# P9-Calculadora.net
KiCad netlist of a schematic drawn in EAGLE
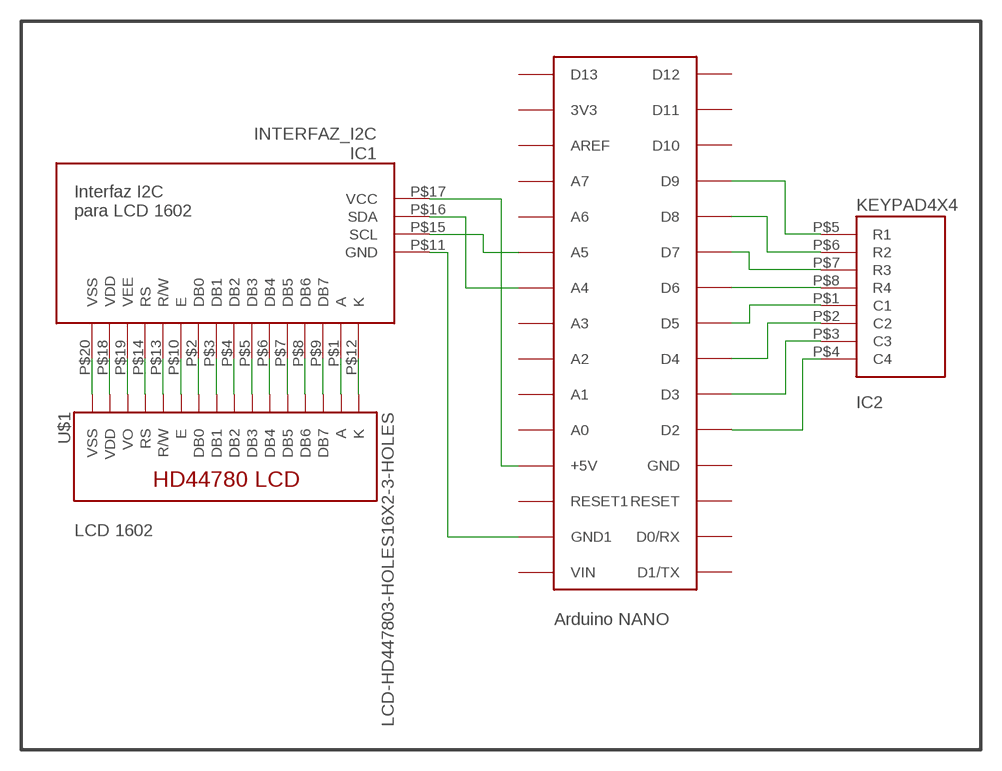
[diagram p0: schematic, sheet 1]

(export (version "E")
  (design (tool "Eeschema 10.0.6"))
  (components
    (comp (ref "IC1")
      (value "INTERFAZ_I2C")
      (footprint "eagle-import:NO_FOOTPRINT")
      (libsource (lib "eagle-import") (part "INTERFAZ_I2C"))
    )
    (comp (ref "IC2")
      (value "KEYPAD4X4")
      (footprint "eagle-import:NO_FOOTPRINT")
      (libsource (lib "eagle-import") (part "KEYPAD4X4"))
    )
    (comp (ref "U$1")
      (value "LCD-HD447803-HOLES16X2-3-HOLES")
      (footprint "eagle-import:LCD-16X2-3HOLES")
      (libsource (lib "eagle-import") (part "LCD-HD4478016X2-3-HOLES3-HOLES"))
    )
    (comp (ref "U$2")
      (value "ARDUINONANO")
      (footprint "eagle-import:PDIP-32")
      (libsource (lib "eagle-import") (part "ARDUINONANO"))
    )
  )
  (nets
    (net (code "1") (name "Net-(IC1-A)") (class "Default")
      (node (ref "IC1") (pin "P$1") (pinfunction "A_P$1") (pintype "bidirectional"))
      (node (ref "U$1") (pin "15") (pinfunction "A_15") (pintype "power_in"))
    )
    (net (code "2") (name "Net-(IC1-DB0)") (class "Default")
      (node (ref "IC1") (pin "P$2") (pinfunction "DB0_P$2") (pintype "bidirectional"))
      (node (ref "U$1") (pin "7") (pinfunction "DB0_7") (pintype "bidirectional"))
    )
    (net (code "3") (name "Net-(IC1-DB1)") (class "Default")
      (node (ref "IC1") (pin "P$3") (pinfunction "DB1_P$3") (pintype "bidirectional"))
      (node (ref "U$1") (pin "8") (pinfunction "DB1_8") (pintype "bidirectional"))
    )
    (net (code "4") (name "Net-(IC1-DB2)") (class "Default")
      (node (ref "IC1") (pin "P$4") (pinfunction "DB2_P$4") (pintype "bidirectional"))
      (node (ref "U$1") (pin "9") (pinfunction "DB2_9") (pintype "bidirectional"))
    )
    (net (code "5") (name "Net-(IC1-DB3)") (class "Default")
      (node (ref "IC1") (pin "P$5") (pinfunction "DB3_P$5") (pintype "bidirectional"))
      (node (ref "U$1") (pin "10") (pinfunction "DB3_10") (pintype "bidirectional"))
    )
    (net (code "6") (name "Net-(IC1-DB4)") (class "Default")
      (node (ref "IC1") (pin "P$6") (pinfunction "DB4_P$6") (pintype "bidirectional"))
      (node (ref "U$1") (pin "11") (pinfunction "DB4_11") (pintype "bidirectional"))
    )
    (net (code "7") (name "Net-(IC1-DB5)") (class "Default")
      (node (ref "IC1") (pin "P$7") (pinfunction "DB5_P$7") (pintype "bidirectional"))
      (node (ref "U$1") (pin "12") (pinfunction "DB5_12") (pintype "bidirectional"))
    )
    (net (code "8") (name "Net-(IC1-DB6)") (class "Default")
      (node (ref "IC1") (pin "P$8") (pinfunction "DB6_P$8") (pintype "bidirectional"))
      (node (ref "U$1") (pin "13") (pinfunction "DB6_13") (pintype "bidirectional"))
    )
    (net (code "9") (name "Net-(IC1-DB7)") (class "Default")
      (node (ref "IC1") (pin "P$9") (pinfunction "DB7_P$9") (pintype "bidirectional"))
      (node (ref "U$1") (pin "14") (pinfunction "DB7_14") (pintype "bidirectional"))
    )
    (net (code "10") (name "Net-(IC1-E)") (class "Default")
      (node (ref "IC1") (pin "P$10") (pinfunction "E_P$10") (pintype "bidirectional"))
      (node (ref "U$1") (pin "6") (pinfunction "E_6") (pintype "input"))
    )
    (net (code "11") (name "Net-(IC1-GND)") (class "Default")
      (node (ref "IC1") (pin "P$11") (pinfunction "GND_P$11") (pintype "bidirectional"))
      (node (ref "U$2") (pin "GND1") (pinfunction "GND1_GND1") (pintype "bidirectional"))
    )
    (net (code "12") (name "Net-(IC1-K)") (class "Default")
      (node (ref "IC1") (pin "P$12") (pinfunction "K_P$12") (pintype "bidirectional"))
      (node (ref "U$1") (pin "16") (pinfunction "K_16") (pintype "power_in"))
    )
    (net (code "13") (name "Net-(IC1-RS)") (class "Default")
      (node (ref "IC1") (pin "P$14") (pinfunction "RS_P$14") (pintype "bidirectional"))
      (node (ref "U$1") (pin "4") (pinfunction "RS_4") (pintype "input"))
    )
    (net (code "14") (name "Net-(IC1-R{slash}W)") (class "Default")
      (node (ref "IC1") (pin "P$13") (pinfunction "R/W_P$13") (pintype "bidirectional"))
      (node (ref "U$1") (pin "5") (pinfunction "R/W_5") (pintype "input"))
    )
    (net (code "15") (name "Net-(IC1-SCL)") (class "Default")
      (node (ref "IC1") (pin "P$15") (pinfunction "SCL_P$15") (pintype "bidirectional"))
      (node (ref "U$2") (pin "A5") (pinfunction "A5_A5") (pintype "bidirectional"))
    )
    (net (code "16") (name "Net-(IC1-SDA)") (class "Default")
      (node (ref "IC1") (pin "P$16") (pinfunction "SDA_P$16") (pintype "bidirectional"))
      (node (ref "U$2") (pin "A4") (pinfunction "A4_A4") (pintype "bidirectional"))
    )
    (net (code "17") (name "Net-(IC1-VCC)") (class "Default")
      (node (ref "IC1") (pin "P$17") (pinfunction "VCC_P$17") (pintype "bidirectional"))
      (node (ref "U$2") (pin "+5V") (pinfunction "+5V_+5V") (pintype "bidirectional"))
    )
    (net (code "18") (name "Net-(IC1-VDD)") (class "Default")
      (node (ref "IC1") (pin "P$18") (pinfunction "VDD_P$18") (pintype "bidirectional"))
      (node (ref "U$1") (pin "2") (pinfunction "VDD_2") (pintype "power_in"))
    )
    (net (code "19") (name "Net-(IC1-VEE)") (class "Default")
      (node (ref "IC1") (pin "P$19") (pinfunction "VEE_P$19") (pintype "bidirectional"))
      (node (ref "U$1") (pin "3") (pinfunction "VO_3") (pintype "bidirectional"))
    )
    (net (code "20") (name "Net-(IC1-VSS)") (class "Default")
      (node (ref "IC1") (pin "P$20") (pinfunction "VSS_P$20") (pintype "bidirectional"))
      (node (ref "U$1") (pin "1") (pinfunction "VSS_1") (pintype "power_in"))
    )
    (net (code "21") (name "Net-(IC2-C1)") (class "Default")
      (node (ref "IC2") (pin "P$1") (pinfunction "C1_P$1") (pintype "bidirectional"))
      (node (ref "U$2") (pin "D5") (pinfunction "D5_D5") (pintype "bidirectional"))
    )
    (net (code "22") (name "Net-(IC2-C2)") (class "Default")
      (node (ref "IC2") (pin "P$2") (pinfunction "C2_P$2") (pintype "bidirectional"))
      (node (ref "U$2") (pin "D4") (pinfunction "D4_D4") (pintype "bidirectional"))
    )
    (net (code "23") (name "Net-(IC2-C3)") (class "Default")
      (node (ref "IC2") (pin "P$3") (pinfunction "C3_P$3") (pintype "bidirectional"))
      (node (ref "U$2") (pin "D3") (pinfunction "D3_D3") (pintype "bidirectional"))
    )
    (net (code "24") (name "Net-(IC2-C4)") (class "Default")
      (node (ref "IC2") (pin "P$4") (pinfunction "C4_P$4") (pintype "bidirectional"))
      (node (ref "U$2") (pin "D2") (pinfunction "D2_D2") (pintype "bidirectional"))
    )
    (net (code "25") (name "Net-(IC2-R1)") (class "Default")
      (node (ref "IC2") (pin "P$5") (pinfunction "R1_P$5") (pintype "bidirectional"))
      (node (ref "U$2") (pin "D9") (pinfunction "D9_D9") (pintype "bidirectional"))
    )
    (net (code "26") (name "Net-(IC2-R2)") (class "Default")
      (node (ref "IC2") (pin "P$6") (pinfunction "R2_P$6") (pintype "bidirectional"))
      (node (ref "U$2") (pin "D8") (pinfunction "D8_D8") (pintype "bidirectional"))
    )
    (net (code "27") (name "Net-(IC2-R3)") (class "Default")
      (node (ref "IC2") (pin "P$7") (pinfunction "R3_P$7") (pintype "bidirectional"))
      (node (ref "U$2") (pin "D7") (pinfunction "D7_D7") (pintype "bidirectional"))
    )
    (net (code "28") (name "Net-(IC2-R4)") (class "Default")
      (node (ref "IC2") (pin "P$8") (pinfunction "R4_P$8") (pintype "bidirectional"))
      (node (ref "U$2") (pin "D6") (pinfunction "D6_D6") (pintype "bidirectional"))
    )
    (net (code "29") (name "unconnected-(U$2-Pad3V3)") (class "Default")
      (node (ref "U$2") (pin "3V3") (pinfunction "3V3_3V3") (pintype "bidirectional"))
    )
    (net (code "30") (name "unconnected-(U$2-PadA0)") (class "Default")
      (node (ref "U$2") (pin "A0") (pinfunction "A0_A0") (pintype "bidirectional"))
    )
    (net (code "31") (name "unconnected-(U$2-PadA1)") (class "Default")
      (node (ref "U$2") (pin "A1") (pinfunction "A1_A1") (pintype "bidirectional"))
    )
    (net (code "32") (name "unconnected-(U$2-PadA2)") (class "Default")
      (node (ref "U$2") (pin "A2") (pinfunction "A2_A2") (pintype "bidirectional"))
    )
    (net (code "33") (name "unconnected-(U$2-PadA3)") (class "Default")
      (node (ref "U$2") (pin "A3") (pinfunction "A3_A3") (pintype "bidirectional"))
    )
    (net (code "34") (name "unconnected-(U$2-PadA6)") (class "Default")
      (node (ref "U$2") (pin "A6") (pinfunction "A6_A6") (pintype "bidirectional"))
    )
    (net (code "35") (name "unconnected-(U$2-PadA7)") (class "Default")
      (node (ref "U$2") (pin "A7") (pinfunction "A7_A7") (pintype "bidirectional"))
    )
    (net (code "36") (name "unconnected-(U$2-PadAREF)") (class "Default")
      (node (ref "U$2") (pin "AREF") (pinfunction "AREF_AREF") (pintype "bidirectional"))
    )
    (net (code "37") (name "unconnected-(U$2-PadD0{slash}RX)") (class "Default")
      (node (ref "U$2") (pin "D0/RX") (pinfunction "D0/RX_D0/RX") (pintype "bidirectional"))
    )
    (net (code "38") (name "unconnected-(U$2-PadD1{slash}TX)") (class "Default")
      (node (ref "U$2") (pin "D1/TX") (pinfunction "D1/TX_D1/TX") (pintype "bidirectional"))
    )
    (net (code "39") (name "unconnected-(U$2-PadD10)") (class "Default")
      (node (ref "U$2") (pin "D10") (pinfunction "D10_D10") (pintype "bidirectional"))
    )
    (net (code "40") (name "unconnected-(U$2-PadD11)") (class "Default")
      (node (ref "U$2") (pin "D11") (pinfunction "D11_D11") (pintype "bidirectional"))
    )
    (net (code "41") (name "unconnected-(U$2-PadD12)") (class "Default")
      (node (ref "U$2") (pin "D12") (pinfunction "D12_D12") (pintype "bidirectional"))
    )
    (net (code "42") (name "unconnected-(U$2-PadD13)") (class "Default")
      (node (ref "U$2") (pin "D13") (pinfunction "D13_D13") (pintype "bidirectional"))
    )
    (net (code "43") (name "unconnected-(U$2-PadGND)") (class "Default")
      (node (ref "U$2") (pin "GND") (pinfunction "GND_GND") (pintype "bidirectional"))
    )
    (net (code "44") (name "unconnected-(U$2-PadRESET)") (class "Default")
      (node (ref "U$2") (pin "RESET") (pinfunction "RESET_RESET") (pintype "bidirectional"))
    )
    (net (code "45") (name "unconnected-(U$2-PadRESET1)") (class "Default")
      (node (ref "U$2") (pin "RESET1") (pinfunction "RESET1_RESET1") (pintype "bidirectional"))
    )
    (net (code "46") (name "unconnected-(U$2-PadVIN)") (class "Default")
      (node (ref "U$2") (pin "VIN") (pinfunction "VIN_VIN") (pintype "bidirectional"))
    )
  )
)
